# Microcontroleur.net
KiCad netlist of a schematic drawn in Altium Designer
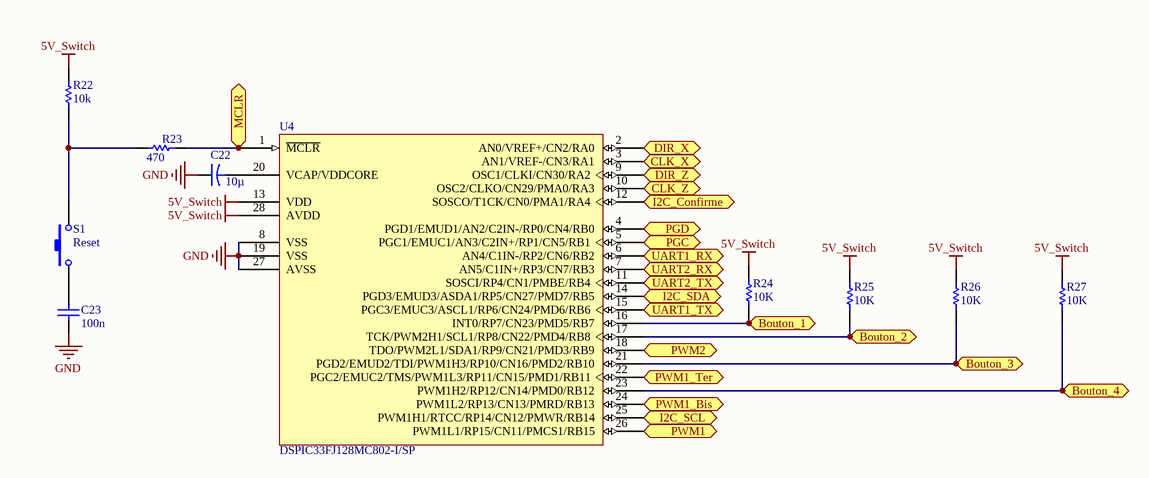
[diagram p0: Microcontroleur.SchDoc]

(export (version "E")
  (design (tool "Eeschema 10.0.6"))
  (components
    (comp (ref "C22")
      (value "10µ")
      (footprint "CAPR5-4X5")
      (fields (field (name "Comment") "Cap2") (field (name "PUBLISHER") "Altium Limited"))
      (libsource (lib "Miscellaneous Devices") (part "Cap2"))
    )
    (comp (ref "C23")
      (value "100n")
      (footprint "RAD-0.3")
      (fields (field (name "Comment") "Cap") (field (name "PUBLISHER") "Altium Limited"))
      (libsource (lib "Miscellaneous Devices") (part "Cap"))
    )
    (comp (ref "R22")
      (value "10k")
      (footprint "AXIAL-0.3")
      (fields (field (name "Comment") "Res1") (field (name "PUBLISHER") "Altium Limited"))
      (libsource (lib "Miscellaneous Devices") (part "Res1"))
    )
    (comp (ref "R23")
      (value "470")
      (footprint "AXIAL-0.3")
      (description "470R")
      (fields (field (name "Comment") "Res1") (field (name "PUBLISHER") "Altium Limited"))
      (libsource (lib "Miscellaneous Devices") (part "Res1"))
    )
    (comp (ref "R24")
      (value "10K")
      (footprint "AXIAL-0.3")
      (description "10k")
      (fields (field (name "Comment") "Res1") (field (name "PUBLISHER") "Altium Limited"))
      (libsource (lib "Miscellaneous Devices") (part "Res1"))
    )
    (comp (ref "R25")
      (value "10K")
      (footprint "AXIAL-0.3")
      (description "10k")
      (fields (field (name "Comment") "Res1") (field (name "PUBLISHER") "Altium Limited"))
      (libsource (lib "Miscellaneous Devices") (part "Res1"))
    )
    (comp (ref "R26")
      (value "10K")
      (footprint "AXIAL-0.3")
      (description "10k")
      (fields (field (name "Comment") "Res1") (field (name "PUBLISHER") "Altium Limited"))
      (libsource (lib "Miscellaneous Devices") (part "Res1"))
    )
    (comp (ref "R27")
      (value "10K")
      (footprint "AXIAL-0.3")
      (description "10k")
      (fields (field (name "Comment") "Res1") (field (name "PUBLISHER") "Altium Limited"))
      (libsource (lib "Miscellaneous Devices") (part "Res1"))
    )
    (comp (ref "S1")
      (value "Reset")
      (footprint "SPST-2")
      (description "Bouton Reset")
      (fields (field (name "PUBLISHER") "Altium Limited"))
      (libsource (lib "Miscellaneous Devices") (part "SW-PB"))
    )
    (comp (ref "U4")
      (value "DSPIC33FJ128MC802-I/SP")
      (footprint "SPDIP300-SP28")
      (fields (field (name "PUBLISHER") "Altium Limited"))
      (libsource (lib "Microchip DSC 16-Bit dsPIC33F") (part "DSPIC33FJ128MC802-I/SP"))
    )
  )
  (nets
    (net (code "1") (name "/Bouton_1") (class "Default")
      (node (ref "R24") (pin "2") (pinfunction "2_2") (pintype "passive"))
      (node (ref "U4") (pin "16") (pinfunction "INT0/RP7/CN23/PMD5/RB7_16") (pintype "bidirectional"))
    )
    (net (code "2") (name "/Bouton_2") (class "Default")
      (node (ref "R25") (pin "2") (pinfunction "2_2") (pintype "passive"))
      (node (ref "U4") (pin "17") (pinfunction "TCK/PWM2H1/SCL1/RP8/CN22/PMD4/RB8_17") (pintype "bidirectional"))
    )
    (net (code "3") (name "/Bouton_3") (class "Default")
      (node (ref "R26") (pin "2") (pinfunction "2_2") (pintype "passive"))
      (node (ref "U4") (pin "21") (pinfunction "PGD2/EMUD2/TDI/PWM1H3/RP10/CN16/PMD2/RB10_21") (pintype "bidirectional"))
    )
    (net (code "4") (name "/Bouton_4") (class "Default")
      (node (ref "R27") (pin "2") (pinfunction "2_2") (pintype "passive"))
      (node (ref "U4") (pin "23") (pinfunction "PWM1H2/RP12/CN14/PMD0/RB12_23") (pintype "bidirectional"))
    )
    (net (code "5") (name "/CLK_X") (class "Default")
      (node (ref "U4") (pin "3") (pinfunction "AN1/VREF-/CN3/RA1_3") (pintype "bidirectional"))
    )
    (net (code "6") (name "/CLK_Z") (class "Default")
      (node (ref "U4") (pin "10") (pinfunction "OSC2/CLKO/CN29/PMA0/RA3_10") (pintype "bidirectional"))
    )
    (net (code "7") (name "/DIR_X") (class "Default")
      (node (ref "U4") (pin "2") (pinfunction "AN0/VREF+/CN2/RA0_2") (pintype "bidirectional"))
    )
    (net (code "8") (name "/DIR_Z") (class "Default")
      (node (ref "U4") (pin "9") (pinfunction "OSC1/CLKI/CN30/RA2_9") (pintype "bidirectional"))
    )
    (net (code "9") (name "/I2C_Confirme") (class "Default")
      (node (ref "U4") (pin "12") (pinfunction "SOSCO/T1CK/CN0/PMA1/RA4_12") (pintype "bidirectional"))
    )
    (net (code "10") (name "/I2C_SCL") (class "Default")
      (node (ref "U4") (pin "25") (pinfunction "PWM1H1/RTCC/RP14/CN12/PMWR/RB14_25") (pintype "bidirectional"))
    )
    (net (code "11") (name "/I2C_SDA") (class "Default")
      (node (ref "U4") (pin "14") (pinfunction "PGD3/EMUD3/ASDA1/RP5/CN27/PMD7/RB5_14") (pintype "bidirectional"))
    )
    (net (code "12") (name "/MCLR") (class "Default")
      (node (ref "R23") (pin "2") (pinfunction "2_2") (pintype "passive"))
      (node (ref "U4") (pin "1") (pinfunction "~{MCLR}_1") (pintype "input"))
    )
    (net (code "13") (name "/PGC") (class "Default")
      (node (ref "U4") (pin "5") (pinfunction "PGC1/EMUC1/AN3/C2IN+/RP1/CN5/RB1_5") (pintype "bidirectional"))
    )
    (net (code "14") (name "/PGD") (class "Default")
      (node (ref "U4") (pin "4") (pinfunction "PGD1/EMUD1/AN2/C2IN-/RP0/CN4/RB0_4") (pintype "bidirectional"))
    )
    (net (code "15") (name "/PWM1") (class "Default")
      (node (ref "U4") (pin "26") (pinfunction "PWM1L1/RP15/CN11/PMCS1/RB15_26") (pintype "bidirectional"))
    )
    (net (code "16") (name "/PWM1_Bis") (class "Default")
      (node (ref "U4") (pin "24") (pinfunction "PWM1L2/RP13/CN13/PMRD/RB13_24") (pintype "bidirectional"))
    )
    (net (code "17") (name "/PWM1_Ter") (class "Default")
      (node (ref "U4") (pin "22") (pinfunction "PGC2/EMUC2/TMS/PWM1L3/RP11/CN15/PMD1/RB11_22") (pintype "bidirectional"))
    )
    (net (code "18") (name "/PWM2") (class "Default")
      (node (ref "U4") (pin "18") (pinfunction "TDO/PWM2L1/SDA1/RP9/CN21/PMD3/RB9_18") (pintype "bidirectional"))
    )
    (net (code "19") (name "/UART1_RX") (class "Default")
      (node (ref "U4") (pin "6") (pinfunction "AN4/C1IN-/RP2/CN6/RB2_6") (pintype "bidirectional"))
    )
    (net (code "20") (name "/UART1_TX") (class "Default")
      (node (ref "U4") (pin "15") (pinfunction "PGC3/EMUC3/ASCL1/RP6/CN24/PMD6/RB6_15") (pintype "bidirectional"))
    )
    (net (code "21") (name "/UART2_RX") (class "Default")
      (node (ref "U4") (pin "7") (pinfunction "AN5/C1IN+/RP3/CN7/RB3_7") (pintype "bidirectional"))
    )
    (net (code "22") (name "/UART2_TX") (class "Default")
      (node (ref "U4") (pin "11") (pinfunction "SOSCI/RP4/CN1/PMBE/RB4_11") (pintype "bidirectional"))
    )
    (net (code "23") (name "5V_Switch") (class "Default")
      (node (ref "R22") (pin "2") (pinfunction "2_2") (pintype "passive"))
      (node (ref "R24") (pin "1") (pinfunction "1_1") (pintype "passive"))
      (node (ref "R25") (pin "1") (pinfunction "1_1") (pintype "passive"))
      (node (ref "R26") (pin "1") (pinfunction "1_1") (pintype "passive"))
      (node (ref "R27") (pin "1") (pinfunction "1_1") (pintype "passive"))
      (node (ref "U4") (pin "13") (pinfunction "VDD_13") (pintype "power_in"))
      (node (ref "U4") (pin "28") (pinfunction "AVDD_28") (pintype "power_in"))
    )
    (net (code "24") (name "GND") (class "Default")
      (node (ref "C22") (pin "1") (pinfunction "1_1") (pintype "passive"))
      (node (ref "C23") (pin "2") (pinfunction "2_2") (pintype "passive"))
      (node (ref "U4") (pin "19") (pinfunction "VSS_19") (pintype "power_in"))
      (node (ref "U4") (pin "27") (pinfunction "AVSS_27") (pintype "power_in"))
      (node (ref "U4") (pin "8") (pinfunction "VSS_8") (pintype "power_in"))
    )
    (net (code "25") (name "Net-(C23-Pad1)") (class "Default")
      (node (ref "C23") (pin "1") (pinfunction "1_1") (pintype "passive"))
      (node (ref "S1") (pin "1") (pinfunction "1_1") (pintype "passive"))
    )
    (net (code "26") (name "Net-(R22-Pad1)") (class "Default")
      (node (ref "R22") (pin "1") (pinfunction "1_1") (pintype "passive"))
      (node (ref "R23") (pin "1") (pinfunction "1_1") (pintype "passive"))
      (node (ref "S1") (pin "2") (pinfunction "2_2") (pintype "passive"))
    )
    (net (code "27") (name "Net-(U4-VCAP{slash}VDDCORE)") (class "Default")
      (node (ref "C22") (pin "2") (pinfunction "2_2") (pintype "passive"))
      (node (ref "U4") (pin "20") (pinfunction "VCAP/VDDCORE_20") (pintype "power_in"))
    )
  )
)
